# MCU.net
KiCad netlist of a schematic drawn in Altium Designer
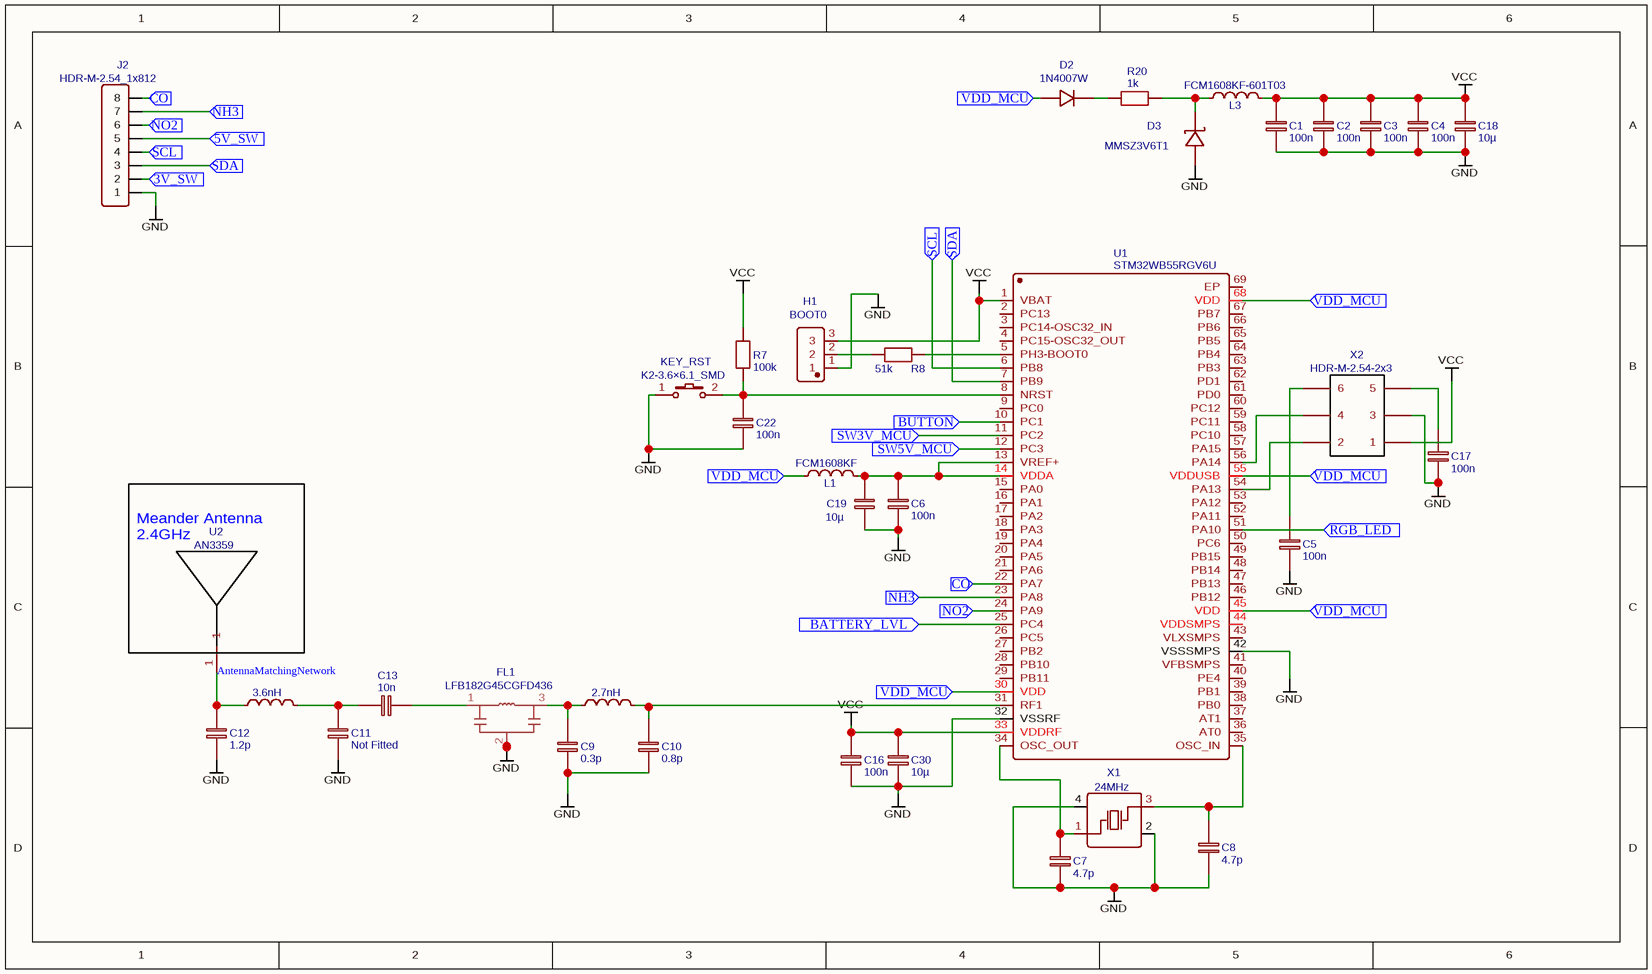
[diagram p0: MCU.schdoc]

(export (version "E")
  (design (tool "Eeschema 10.0.6"))
  (components
    (comp (ref "C1")
      (value "100n")
      (fields (field (name "CONTRIBUTOR") "LCEDA_Lib"))
      (libsource (lib "altium-import") (part "root_1_100n_"))
    )
    (comp (ref "C2")
      (value "100n")
      (fields (field (name "CONTRIBUTOR") "LCEDA_Lib"))
      (libsource (lib "altium-import") (part "root_1_100n_"))
    )
    (comp (ref "C3")
      (value "100n")
      (fields (field (name "CONTRIBUTOR") "LCEDA_Lib"))
      (libsource (lib "altium-import") (part "root_1_100n_"))
    )
    (comp (ref "C4")
      (value "100n")
      (fields (field (name "CONTRIBUTOR") "LCEDA_Lib"))
      (libsource (lib "altium-import") (part "root_1_100n_"))
    )
    (comp (ref "C5")
      (value "100n")
      (fields (field (name "CONTRIBUTOR") "LCEDA_Lib"))
      (libsource (lib "altium-import") (part "root_1_100n_"))
    )
    (comp (ref "C6")
      (value "100n")
      (fields (field (name "CONTRIBUTOR") "LCEDA_Lib"))
      (libsource (lib "altium-import") (part "root_1_100n_"))
    )
    (comp (ref "C7")
      (value "4.7p")
      (fields (field (name "CONTRIBUTOR") "LCEDA_Lib"))
      (libsource (lib "altium-import") (part "root_1_4.7p_"))
    )
    (comp (ref "C8")
      (value "4.7p")
      (fields (field (name "CONTRIBUTOR") "LCEDA_Lib"))
      (libsource (lib "altium-import") (part "root_1_4.7p_"))
    )
    (comp (ref "C9")
      (value "0.3p")
      (fields (field (name "CONTRIBUTOR") "LCEDA_Lib"))
      (libsource (lib "altium-import") (part "root_1_0.3p_"))
    )
    (comp (ref "C10")
      (value "0.8p")
      (fields (field (name "CONTRIBUTOR") "LCEDA_Lib"))
      (libsource (lib "altium-import") (part "root_1_0.8p_"))
    )
    (comp (ref "C11")
      (value "Not Fitted")
      (fields (field (name "CONTRIBUTOR") "LCEDA_Lib"))
      (libsource (lib "altium-import") (part "root_1_Not Fitted_"))
    )
    (comp (ref "C12")
      (value "1.2p")
      (fields (field (name "CONTRIBUTOR") "LCEDA_Lib"))
      (libsource (lib "altium-import") (part "root_1_1.2p_"))
    )
    (comp (ref "C13")
      (value "10n")
      (fields (field (name "CONTRIBUTOR") "LCEDA_Lib"))
      (libsource (lib "altium-import") (part "root_2_10n_"))
    )
    (comp (ref "C16")
      (value "100n")
      (fields (field (name "CONTRIBUTOR") "LCEDA_Lib"))
      (libsource (lib "altium-import") (part "root_1_100n_"))
    )
    (comp (ref "C17")
      (value "100n")
      (fields (field (name "CONTRIBUTOR") "LCEDA_Lib"))
      (libsource (lib "altium-import") (part "root_1_100n_"))
    )
    (comp (ref "C18")
      (value "10µ")
      (fields (field (name "CONTRIBUTOR") "LCEDA_Lib"))
      (libsource (lib "altium-import") (part "root_1_10µ_"))
    )
    (comp (ref "C19")
      (value "10µ")
      (fields (field (name "CONTRIBUTOR") "LCEDA_Lib"))
      (libsource (lib "altium-import") (part "root_1_10µ_"))
    )
    (comp (ref "C22")
      (value "100n")
      (fields (field (name "CONTRIBUTOR") "LCEDA_Lib"))
      (libsource (lib "altium-import") (part "root_1_100n_"))
    )
    (comp (ref "C30")
      (value "10µ")
      (fields (field (name "CONTRIBUTOR") "LCEDA_Lib"))
      (libsource (lib "altium-import") (part "root_1_10µ_"))
    )
    (comp (ref "D2")
      (value "1N4007W")
      (fields (field (name "BOM_SUPPLIER PART") "C328592") (field (name "CONTRIBUTOR") "LCEDA_Lib"))
      (libsource (lib "altium-import") (part "root_0_1N4007W_"))
    )
    (comp (ref "D3")
      (value "MMSZ3V6T1")
      (fields
        (field (name "BOM_SUPPLIER PART") "C9900023612")
        (field (name "BOM_MANUFACTURER PART") "DIODEZENER3.3V500MWSOD-523")
        (field (name "CONTRIBUTOR") "lcsc")
      )
      (libsource (lib "altium-import") (part "root_3_MMSZ3V6T1_"))
    )
    (comp (ref "FL1")
      (value "LFB182G45CGFD436")
      (fields (field (name "CONTRIBUTOR") "Anderson Macedo"))
      (libsource (lib "altium-import") (part "root_0_LFB182G45CGFD436_"))
    )
    (comp (ref "H1")
      (value "BOOT0")
      (fields
        (field (name "BOM_SUPPLIER PART") "C2894926")
        (field (name "BOM_MANUFACTURER PART") "PZ254-1-03-Z-8.5")
        (field (name "CONTRIBUTOR") "LCSC")
      )
      (libsource (lib "altium-import") (part "root_2_BOOT0_"))
    )
    (comp (ref "J2")
      (value "HDR-M-2.54_1x812")
      (fields (field (name "BOM_SUPPLIER PART") "C190820") (field (name "CONTRIBUTOR") "Hane_Jared"))
      (libsource (lib "altium-import") (part "root_2_HDR-M-2.54_1x812_"))
    )
    (comp (ref "KEY_RST")
      (value "K2-3.6×6.1_SMD")
      (fields
        (field (name "BOM_SUPPLIER PART") "C118141")
        (field (name "BOM_MANUFACTURER PART") "K2-1107ST-A4SW-06")
        (field (name "CONTRIBUTOR") "LCEDA_Lib")
      )
      (libsource (lib "altium-import") (part "root_0_K2-3.6×6.1_SMD_"))
    )
    (comp (ref "L")
      (value "3.6nH")
      (fields
        (field (name "BOM_MANUFACTURER PART") "LQG15HS3N6S02D")
        (field (name "BOM_SUPPLIER PART") "81-LQG15HS3N6S02D")
        (field (name "CONTRIBUTOR") "cyrilledecourtois")
      )
      (libsource (lib "altium-import") (part "root_0_3.6nH_"))
    )
    (comp (ref "L1")
      (value "FCM1608KF")
      (fields
        (field (name "BOM_SUPPLIER PART") "C141723")
        (field (name "BOM_MANUFACTURER PART") "FCM1608KF-601T03")
        (field (name "CONTRIBUTOR") "LCSC")
      )
      (libsource (lib "altium-import") (part "root_0_FCM1608KF_"))
    )
    (comp (ref "L3")
      (value "FCM1608KF-601T03")
      (fields (field (name "BOM_SUPPLIER PART") "C141723") (field (name "CONTRIBUTOR") "LCSC"))
      (libsource (lib "altium-import") (part "root_0_FCM1608KF-601T03_"))
    )
    (comp (ref "NO")
      (value "2.7nH")
      (fields
        (field (name "BOM_MANUFACTURER PART") "LQG15HS2N7S02D")
        (field (name "BOM_SUPPLIER PART") "81-LQG15HS2N7S02D")
        (field (name "CONTRIBUTOR") "cyrilledecourtois")
      )
      (libsource (lib "altium-import") (part "root_0_2.7nH_"))
    )
    (comp (ref "R7")
      (value "100k")
      (fields (field (name "CONTRIBUTOR") "LCEDA_Lib"))
      (libsource (lib "altium-import") (part "root_3_100k_"))
    )
    (comp (ref "R8")
      (value "51k")
      (fields (field (name "CONTRIBUTOR") "LCEDA_Lib"))
      (libsource (lib "altium-import") (part "root_0_51k_"))
    )
    (comp (ref "R20")
      (value "1k")
      (fields (field (name "CONTRIBUTOR") "LCEDA_Lib"))
      (libsource (lib "altium-import") (part "root_0_1k_"))
    )
    (comp (ref "U1")
      (value "STM32WB55RGV6U")
      (fields (field (name "BOM_SUPPLIER PART") "C1558433") (field (name "CONTRIBUTOR") "LCSC"))
      (libsource (lib "altium-import") (part "root_0_STM32WB55RGV6U_"))
    )
    (comp (ref "U2")
      (value "AN3359")
      (fields (field (name "CONTRIBUTOR") "ktw07182"))
      (libsource (lib "altium-import") (part "root_1_AN3359_"))
    )
    (comp (ref "X1")
      (value "24MHz")
      (fields
        (field (name "BOM_SUPPLIER PART") "C1986620")
        (field (name "BOM_MANUFACTURER PART") "ABM8AIG-24.000MHZ-R40-4-T")
        (field (name "CONTRIBUTOR") "LCSC")
      )
      (libsource (lib "altium-import") (part "root_0_24MHz_"))
    )
    (comp (ref "X2")
      (value "HDR-M-2.54-2x3")
      (fields (field (name "CONTRIBUTOR") "dalex806"))
      (libsource (lib "altium-import") (part "root_2_HDR-M-2.54-2x3_"))
    )
  )
  (nets
    (net (code "1") (name "/3V_SW") (class "Default")
      (node (ref "J2") (pin "2") (pinfunction "2_2") (pintype "passive"))
    )
    (net (code "2") (name "/5V_SW") (class "Default")
      (node (ref "J2") (pin "5") (pinfunction "5_5") (pintype "passive"))
    )
    (net (code "3") (name "/AntennaMatchingNetwork") (class "Default")
      (node (ref "C12") (pin "2") (pinfunction "2_2") (pintype "passive"))
      (node (ref "L") (pin "1") (pinfunction "1_1") (pintype "passive"))
      (node (ref "U2") (pin "1") (pinfunction "1_1") (pintype "passive"))
    )
    (net (code "4") (name "/BATTERY_LVL") (class "Default")
      (node (ref "U1") (pin "25") (pinfunction "PC4_25") (pintype "passive"))
    )
    (net (code "5") (name "/BUTTON") (class "Default")
      (node (ref "U1") (pin "10") (pinfunction "PC1_10") (pintype "passive"))
    )
    (net (code "6") (name "/CO") (class "Default")
      (node (ref "J2") (pin "8") (pinfunction "8_8") (pintype "passive"))
      (node (ref "U1") (pin "22") (pinfunction "PA7_22") (pintype "passive"))
    )
    (net (code "7") (name "/NH3") (class "Default")
      (node (ref "J2") (pin "7") (pinfunction "7_7") (pintype "passive"))
      (node (ref "U1") (pin "23") (pinfunction "PA8_23") (pintype "passive"))
    )
    (net (code "8") (name "/NO2") (class "Default")
      (node (ref "J2") (pin "6") (pinfunction "6_6") (pintype "passive"))
      (node (ref "U1") (pin "24") (pinfunction "PA9_24") (pintype "passive"))
    )
    (net (code "9") (name "/RGB_LED") (class "Default")
      (node (ref "U1") (pin "51") (pinfunction "PA10_51") (pintype "passive"))
    )
    (net (code "10") (name "/SCL") (class "Default")
      (node (ref "J2") (pin "4") (pinfunction "4_4") (pintype "passive"))
      (node (ref "U1") (pin "6") (pinfunction "PB8_6") (pintype "passive"))
    )
    (net (code "11") (name "/SDA") (class "Default")
      (node (ref "J2") (pin "3") (pinfunction "3_3") (pintype "passive"))
      (node (ref "U1") (pin "7") (pinfunction "PB9_7") (pintype "passive"))
    )
    (net (code "12") (name "/SW3V_MCU") (class "Default")
      (node (ref "U1") (pin "11") (pinfunction "PC2_11") (pintype "passive"))
    )
    (net (code "13") (name "/SW5V_MCU") (class "Default")
      (node (ref "U1") (pin "12") (pinfunction "PC3_12") (pintype "passive"))
    )
    (net (code "14") (name "/VDD_MCU") (class "Default")
      (node (ref "D2") (pin "2") (pinfunction "2_2") (pintype "passive"))
      (node (ref "L1") (pin "1") (pinfunction "1_1") (pintype "passive"))
      (node (ref "U1") (pin "30") (pinfunction "VDD_30") (pintype "passive"))
      (node (ref "U1") (pin "45") (pinfunction "VDD_45") (pintype "passive"))
      (node (ref "U1") (pin "55") (pinfunction "VDDUSB_55") (pintype "passive"))
      (node (ref "U1") (pin "68") (pinfunction "VDD_68") (pintype "passive"))
    )
    (net (code "15") (name "GND") (class "Default")
      (node (ref "C1") (pin "1") (pinfunction "1_1") (pintype "passive"))
      (node (ref "C10") (pin "1") (pinfunction "1_1") (pintype "passive"))
      (node (ref "C11") (pin "1") (pinfunction "1_1") (pintype "passive"))
      (node (ref "C12") (pin "1") (pinfunction "1_1") (pintype "passive"))
      (node (ref "C16") (pin "1") (pinfunction "1_1") (pintype "passive"))
      (node (ref "C17") (pin "1") (pinfunction "1_1") (pintype "passive"))
      (node (ref "C18") (pin "1") (pinfunction "1_1") (pintype "passive"))
      (node (ref "C19") (pin "1") (pinfunction "1_1") (pintype "passive"))
      (node (ref "C2") (pin "1") (pinfunction "1_1") (pintype "passive"))
      (node (ref "C22") (pin "1") (pinfunction "1_1") (pintype "passive"))
      (node (ref "C3") (pin "1") (pinfunction "1_1") (pintype "passive"))
      (node (ref "C30") (pin "1") (pinfunction "1_1") (pintype "passive"))
      (node (ref "C4") (pin "1") (pinfunction "1_1") (pintype "passive"))
      (node (ref "C5") (pin "1") (pinfunction "1_1") (pintype "passive"))
      (node (ref "C6") (pin "1") (pinfunction "1_1") (pintype "passive"))
      (node (ref "C7") (pin "1") (pinfunction "1_1") (pintype "passive"))
      (node (ref "C8") (pin "1") (pinfunction "1_1") (pintype "passive"))
      (node (ref "C9") (pin "1") (pinfunction "1_1") (pintype "passive"))
      (node (ref "D3") (pin "2") (pinfunction "A_2") (pintype "passive"))
      (node (ref "FL1") (pin "2") (pinfunction "GND_2") (pintype "passive"))
      (node (ref "FL1") (pin "2_1") (pinfunction "GND_2_1") (pintype "passive"))
      (node (ref "H1") (pin "1") (pinfunction "1_1") (pintype "passive"))
      (node (ref "J2") (pin "1") (pinfunction "1_1") (pintype "passive"))
      (node (ref "KEY_RST") (pin "1") (pinfunction "1_1") (pintype "passive"))
      (node (ref "U1") (pin "32") (pinfunction "VSSRF_32") (pintype "passive"))
      (node (ref "U1") (pin "42") (pinfunction "VSSSMPS_42") (pintype "passive"))
      (node (ref "X1") (pin "2") (pinfunction "GND_2") (pintype "passive"))
      (node (ref "X1") (pin "4") (pinfunction "GND_4") (pintype "passive"))
      (node (ref "X2") (pin "3") (pinfunction "3_3") (pintype "passive"))
    )
    (net (code "16") (name "Net-(C5-Pad2)") (class "Default")
      (node (ref "C5") (pin "2") (pinfunction "2_2") (pintype "passive"))
      (node (ref "X2") (pin "6") (pinfunction "6_6") (pintype "passive"))
    )
    (net (code "17") (name "Net-(C11-Pad2)") (class "Default")
      (node (ref "C11") (pin "2") (pinfunction "2_2") (pintype "passive"))
      (node (ref "C13") (pin "2") (pinfunction "2_2") (pintype "passive"))
      (node (ref "L") (pin "2") (pinfunction "2_2") (pintype "passive"))
    )
    (net (code "18") (name "Net-(C17-Pad2)") (class "Default")
      (node (ref "C17") (pin "2") (pinfunction "2_2") (pintype "passive"))
      (node (ref "X2") (pin "5") (pinfunction "5_5") (pintype "passive"))
    )
    (net (code "19") (name "Net-(D2-Pad1)") (class "Default")
      (node (ref "D2") (pin "1") (pinfunction "1_1") (pintype "passive"))
      (node (ref "R20") (pin "1") (pinfunction "1_1") (pintype "passive"))
    )
    (net (code "20") (name "Net-(D3-K)") (class "Default")
      (node (ref "D3") (pin "1") (pinfunction "K_1") (pintype "passive"))
      (node (ref "L3") (pin "1") (pinfunction "1_1") (pintype "passive"))
      (node (ref "R20") (pin "2") (pinfunction "2_2") (pintype "passive"))
    )
    (net (code "21") (name "Net-(FL1-IN)") (class "Default")
      (node (ref "C13") (pin "1") (pinfunction "1_1") (pintype "passive"))
      (node (ref "FL1") (pin "1") (pinfunction "IN_1") (pintype "passive"))
    )
    (net (code "22") (name "Net-(FL1-OUT)") (class "Default")
      (node (ref "C9") (pin "2") (pinfunction "2_2") (pintype "passive"))
      (node (ref "FL1") (pin "3") (pinfunction "OUT_3") (pintype "passive"))
      (node (ref "NO") (pin "1") (pinfunction "1_1") (pintype "passive"))
    )
    (net (code "23") (name "Net-(H1-Pad2)") (class "Default")
      (node (ref "H1") (pin "2") (pinfunction "2_2") (pintype "passive"))
      (node (ref "R8") (pin "1") (pinfunction "1_1") (pintype "passive"))
    )
    (net (code "24") (name "Net-(U1-NRST)") (class "Default")
      (node (ref "C22") (pin "2") (pinfunction "2_2") (pintype "passive"))
      (node (ref "KEY_RST") (pin "2") (pinfunction "2_2") (pintype "passive"))
      (node (ref "R7") (pin "2") (pinfunction "2_2") (pintype "passive"))
      (node (ref "U1") (pin "8") (pinfunction "NRST_8") (pintype "passive"))
    )
    (net (code "25") (name "Net-(U1-OSC_IN)") (class "Default")
      (node (ref "C8") (pin "2") (pinfunction "2_2") (pintype "passive"))
      (node (ref "U1") (pin "35") (pinfunction "OSC_IN_35") (pintype "passive"))
      (node (ref "X1") (pin "3") (pinfunction "OSC2_3") (pintype "passive"))
    )
    (net (code "26") (name "Net-(U1-OSC_OUT)") (class "Default")
      (node (ref "C7") (pin "2") (pinfunction "2_2") (pintype "passive"))
      (node (ref "U1") (pin "34") (pinfunction "OSC_OUT_34") (pintype "passive"))
      (node (ref "X1") (pin "1") (pinfunction "OSC1_1") (pintype "passive"))
    )
    (net (code "27") (name "Net-(U1-PA13)") (class "Default")
      (node (ref "U1") (pin "54") (pinfunction "PA13_54") (pintype "passive"))
      (node (ref "X2") (pin "2") (pinfunction "2_2") (pintype "passive"))
    )
    (net (code "28") (name "Net-(U1-PA14)") (class "Default")
      (node (ref "U1") (pin "56") (pinfunction "PA14_56") (pintype "passive"))
      (node (ref "X2") (pin "4") (pinfunction "4_4") (pintype "passive"))
    )
    (net (code "29") (name "Net-(U1-PH3-BOOT0)") (class "Default")
      (node (ref "R8") (pin "2") (pinfunction "2_2") (pintype "passive"))
      (node (ref "U1") (pin "5") (pinfunction "PH3-BOOT0_5") (pintype "passive"))
    )
    (net (code "30") (name "Net-(U1-RF1)") (class "Default")
      (node (ref "C10") (pin "2") (pinfunction "2_2") (pintype "passive"))
      (node (ref "NO") (pin "2") (pinfunction "2_2") (pintype "passive"))
      (node (ref "U1") (pin "31") (pinfunction "RF1_31") (pintype "passive"))
    )
    (net (code "31") (name "Net-(U1-VDDA)") (class "Default")
      (node (ref "C19") (pin "2") (pinfunction "2_2") (pintype "passive"))
      (node (ref "C6") (pin "2") (pinfunction "2_2") (pintype "passive"))
      (node (ref "L1") (pin "2") (pinfunction "2_2") (pintype "passive"))
      (node (ref "U1") (pin "13") (pinfunction "VREF+_13") (pintype "passive"))
      (node (ref "U1") (pin "14") (pinfunction "VDDA_14") (pintype "passive"))
    )
    (net (code "32") (name "VCC") (class "Default")
      (node (ref "C1") (pin "2") (pinfunction "2_2") (pintype "passive"))
      (node (ref "C16") (pin "2") (pinfunction "2_2") (pintype "passive"))
      (node (ref "C18") (pin "2") (pinfunction "2_2") (pintype "passive"))
      (node (ref "C2") (pin "2") (pinfunction "2_2") (pintype "passive"))
      (node (ref "C3") (pin "2") (pinfunction "2_2") (pintype "passive"))
      (node (ref "C30") (pin "2") (pinfunction "2_2") (pintype "passive"))
      (node (ref "C4") (pin "2") (pinfunction "2_2") (pintype "passive"))
      (node (ref "H1") (pin "3") (pinfunction "3_3") (pintype "passive"))
      (node (ref "L3") (pin "2") (pinfunction "2_2") (pintype "passive"))
      (node (ref "R7") (pin "1") (pinfunction "1_1") (pintype "passive"))
      (node (ref "U1") (pin "1") (pinfunction "VBAT_1") (pintype "passive"))
      (node (ref "U1") (pin "33") (pinfunction "VDDRF_33") (pintype "passive"))
      (node (ref "X2") (pin "1") (pinfunction "1_1") (pintype "passive"))
    )
    (net (code "33") (name "unconnected-(U1-AT0-Pad36)") (class "Default")
      (node (ref "U1") (pin "36") (pinfunction "AT0_36") (pintype "passive"))
    )
    (net (code "34") (name "unconnected-(U1-AT1-Pad37)") (class "Default")
      (node (ref "U1") (pin "37") (pinfunction "AT1_37") (pintype "passive"))
    )
    (net (code "35") (name "unconnected-(U1-EP-Pad69)") (class "Default")
      (node (ref "U1") (pin "69") (pinfunction "EP_69") (pintype "passive"))
    )
    (net (code "36") (name "unconnected-(U1-PA0-Pad15)") (class "Default")
      (node (ref "U1") (pin "15") (pinfunction "PA0_15") (pintype "passive"))
    )
    (net (code "37") (name "unconnected-(U1-PA1-Pad16)") (class "Default")
      (node (ref "U1") (pin "16") (pinfunction "PA1_16") (pintype "passive"))
    )
    (net (code "38") (name "unconnected-(U1-PA2-Pad17)") (class "Default")
      (node (ref "U1") (pin "17") (pinfunction "PA2_17") (pintype "passive"))
    )
    (net (code "39") (name "unconnected-(U1-PA3-Pad18)") (class "Default")
      (node (ref "U1") (pin "18") (pinfunction "PA3_18") (pintype "passive"))
    )
    (net (code "40") (name "unconnected-(U1-PA4-Pad19)") (class "Default")
      (node (ref "U1") (pin "19") (pinfunction "PA4_19") (pintype "passive"))
    )
    (net (code "41") (name "unconnected-(U1-PA5-Pad20)") (class "Default")
      (node (ref "U1") (pin "20") (pinfunction "PA5_20") (pintype "passive"))
    )
    (net (code "42") (name "unconnected-(U1-PA6-Pad21)") (class "Default")
      (node (ref "U1") (pin "21") (pinfunction "PA6_21") (pintype "passive"))
    )
    (net (code "43") (name "unconnected-(U1-PA11-Pad52)") (class "Default")
      (node (ref "U1") (pin "52") (pinfunction "PA11_52") (pintype "passive"))
    )
    (net (code "44") (name "unconnected-(U1-PA12-Pad53)") (class "Default")
      (node (ref "U1") (pin "53") (pinfunction "PA12_53") (pintype "passive"))
    )
    (net (code "45") (name "unconnected-(U1-PA15-Pad57)") (class "Default")
      (node (ref "U1") (pin "57") (pinfunction "PA15_57") (pintype "passive"))
    )
    (net (code "46") (name "unconnected-(U1-PB0-Pad38)") (class "Default")
      (node (ref "U1") (pin "38") (pinfunction "PB0_38") (pintype "passive"))
    )
    (net (code "47") (name "unconnected-(U1-PB1-Pad39)") (class "Default")
      (node (ref "U1") (pin "39") (pinfunction "PB1_39") (pintype "passive"))
    )
    (net (code "48") (name "unconnected-(U1-PB2-Pad27)") (class "Default")
      (node (ref "U1") (pin "27") (pinfunction "PB2_27") (pintype "passive"))
    )
    (net (code "49") (name "unconnected-(U1-PB3-Pad63)") (class "Default")
      (node (ref "U1") (pin "63") (pinfunction "PB3_63") (pintype "passive"))
    )
    (net (code "50") (name "unconnected-(U1-PB4-Pad64)") (class "Default")
      (node (ref "U1") (pin "64") (pinfunction "PB4_64") (pintype "passive"))
    )
    (net (code "51") (name "unconnected-(U1-PB5-Pad65)") (class "Default")
      (node (ref "U1") (pin "65") (pinfunction "PB5_65") (pintype "passive"))
    )
    (net (code "52") (name "unconnected-(U1-PB6-Pad66)") (class "Default")
      (node (ref "U1") (pin "66") (pinfunction "PB6_66") (pintype "passive"))
    )
    (net (code "53") (name "unconnected-(U1-PB7-Pad67)") (class "Default")
      (node (ref "U1") (pin "67") (pinfunction "PB7_67") (pintype "passive"))
    )
    (net (code "54") (name "unconnected-(U1-PB10-Pad28)") (class "Default")
      (node (ref "U1") (pin "28") (pinfunction "PB10_28") (pintype "passive"))
    )
    (net (code "55") (name "unconnected-(U1-PB11-Pad29)") (class "Default")
      (node (ref "U1") (pin "29") (pinfunction "PB11_29") (pintype "passive"))
    )
    (net (code "56") (name "unconnected-(U1-PB12-Pad46)") (class "Default")
      (node (ref "U1") (pin "46") (pinfunction "PB12_46") (pintype "passive"))
    )
    (net (code "57") (name "unconnected-(U1-PB13-Pad47)") (class "Default")
      (node (ref "U1") (pin "47") (pinfunction "PB13_47") (pintype "passive"))
    )
    (net (code "58") (name "unconnected-(U1-PB14-Pad48)") (class "Default")
      (node (ref "U1") (pin "48") (pinfunction "PB14_48") (pintype "passive"))
    )
    (net (code "59") (name "unconnected-(U1-PB15-Pad49)") (class "Default")
      (node (ref "U1") (pin "49") (pinfunction "PB15_49") (pintype "passive"))
    )
    (net (code "60") (name "unconnected-(U1-PC0-Pad9)") (class "Default")
      (node (ref "U1") (pin "9") (pinfunction "PC0_9") (pintype "passive"))
    )
    (net (code "61") (name "unconnected-(U1-PC5-Pad26)") (class "Default")
      (node (ref "U1") (pin "26") (pinfunction "PC5_26") (pintype "passive"))
    )
    (net (code "62") (name "unconnected-(U1-PC6-Pad50)") (class "Default")
      (node (ref "U1") (pin "50") (pinfunction "PC6_50") (pintype "passive"))
    )
    (net (code "63") (name "unconnected-(U1-PC10-Pad58)") (class "Default")
      (node (ref "U1") (pin "58") (pinfunction "PC10_58") (pintype "passive"))
    )
    (net (code "64") (name "unconnected-(U1-PC11-Pad59)") (class "Default")
      (node (ref "U1") (pin "59") (pinfunction "PC11_59") (pintype "passive"))
    )
    (net (code "65") (name "unconnected-(U1-PC12-Pad60)") (class "Default")
      (node (ref "U1") (pin "60") (pinfunction "PC12_60") (pintype "passive"))
    )
    (net (code "66") (name "unconnected-(U1-PC13-Pad2)") (class "Default")
      (node (ref "U1") (pin "2") (pinfunction "PC13_2") (pintype "passive"))
    )
    (net (code "67") (name "unconnected-(U1-PC14-OSC32_IN-Pad3)") (class "Default")
      (node (ref "U1") (pin "3") (pinfunction "PC14-OSC32_IN_3") (pintype "passive"))
    )
    (net (code "68") (name "unconnected-(U1-PC15-OSC32_OUT-Pad4)") (class "Default")
      (node (ref "U1") (pin "4") (pinfunction "PC15-OSC32_OUT_4") (pintype "passive"))
    )
    (net (code "69") (name "unconnected-(U1-PD0-Pad61)") (class "Default")
      (node (ref "U1") (pin "61") (pinfunction "PD0_61") (pintype "passive"))
    )
    (net (code "70") (name "unconnected-(U1-PD1-Pad62)") (class "Default")
      (node (ref "U1") (pin "62") (pinfunction "PD1_62") (pintype "passive"))
    )
    (net (code "71") (name "unconnected-(U1-PE4-Pad40)") (class "Default")
      (node (ref "U1") (pin "40") (pinfunction "PE4_40") (pintype "passive"))
    )
    (net (code "72") (name "unconnected-(U1-VDDSMPS-Pad44)") (class "Default")
      (node (ref "U1") (pin "44") (pinfunction "VDDSMPS_44") (pintype "passive"))
    )
    (net (code "73") (name "unconnected-(U1-VFBSMPS-Pad41)") (class "Default")
      (node (ref "U1") (pin "41") (pinfunction "VFBSMPS_41") (pintype "passive"))
    )
    (net (code "74") (name "unconnected-(U1-VLXSMPS-Pad43)") (class "Default")
      (node (ref "U1") (pin "43") (pinfunction "VLXSMPS_43") (pintype "passive"))
    )
  )
)
